# BS01_and_BA01_Connectors.net
KiCad netlist of a schematic drawn in Altium Designer
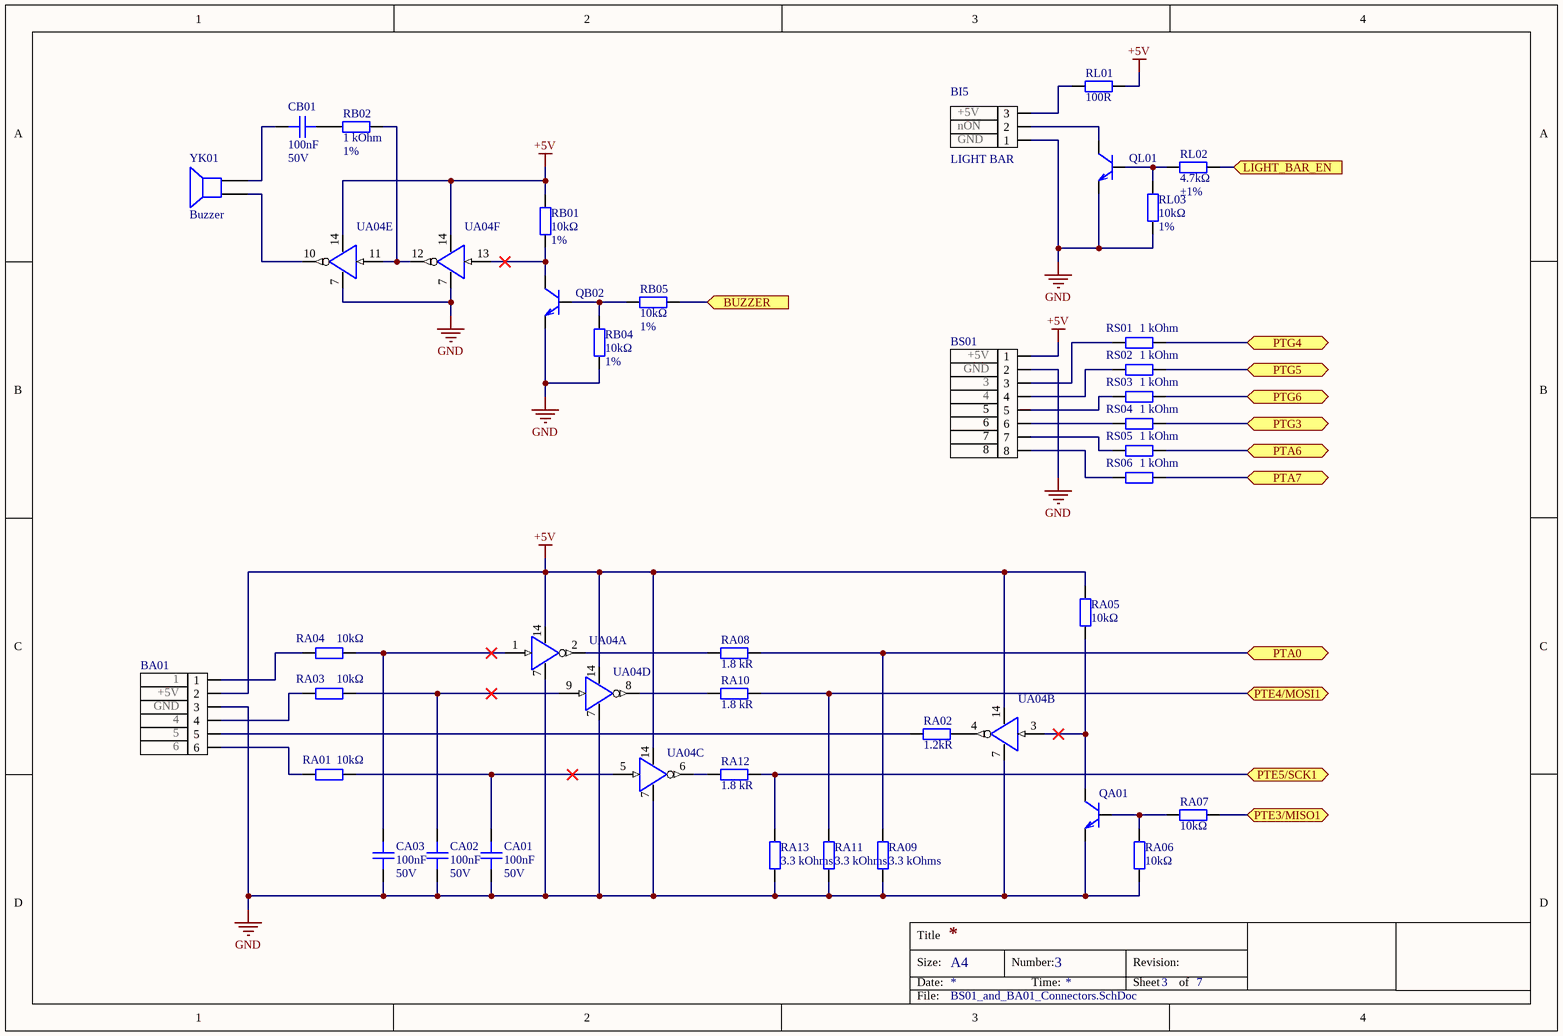
[diagram p0: BS01_and_BA01_Connectors.SchDoc]

(export (version "E")
  (design (tool "Eeschema 10.0.6"))
  (components
    (comp (ref "BA01")
      (value "Comment")
      (fields
        (field (name "PIN_1") "1")
        (field (name "PIN_2") "+5V")
        (field (name "PIN_3") "GND")
        (field (name "PIN_4") "4")
        (field (name "PIN_5") "5")
        (field (name "PIN_6") "6")
      )
      (libsource (lib "connectors_header") (part "CONN HEADER EC 6POS"))
    )
    (comp (ref "BI5")
      (value "LIGHT BAR")
      (footprint "CONN_S3B-ZR_JST")
      (description "Connector Header Through Hole, Right Angle 3 position 0.059\" (1.50mm)")
      (fields
        (field (name "MANUFACTURER") "JST")
        (field (name "MANUFACTURER PART NUMBER") "S3B-ZR(LF)(SN)")
        (field (name "PIN_1") "GND")
        (field (name "PIN_2") "nON")
        (field (name "PIN_3") "+5V")
      )
      (libsource (lib "connectors_header") (part "CONN HEADER TH R/A 3POS 1.5MM"))
    )
    (comp (ref "BS01")
      (value "CONN HEADER R/A 8POS 2.54MM")
      (footprint "CONN HEADER R/A 8POS 2.54MM")
      (description "Connector Header Through Hole, Right Angle 8 position 0.100\" (2.54mm)")
      (fields
        (field (name "PIN_1") "+5V")
        (field (name "PIN_2") "GND")
        (field (name "PIN_3") "3")
        (field (name "PIN_4") "4")
        (field (name "PIN_7") "7")
        (field (name "PIN_5") "5")
        (field (name "PIN_6") "6")
        (field (name "PIN_8") "8")
      )
      (libsource (lib "connectors_header") (part "CONN HEADER R/A 8POS 2.54MM"))
    )
    (comp (ref "CA01")
      (value "CAP CER 0.1uF ±10% 50V X7R 0603")
      (footprint "CAPC1608X08N_0603")
      (description "Capacitor")
      (fields
        (field (name "MANUFACTURER") "KEMET")
        (field (name "MANUFACTURER PART NUMBER") "C0603C104M5RACTU")
        (field (name "CAPACITANCE") "100nF")
        (field (name "VOLTAGE RATING") "50V")
      )
      (libsource (lib "capacitors_smd") (part "CAP CER 0.1uF ±10% 50V X7R 0603"))
    )
    (comp (ref "CA02")
      (value "CAP CER 0.1uF ±10% 50V X7R 0603")
      (footprint "CAPC1608X08N_0603")
      (description "Capacitor")
      (fields
        (field (name "MANUFACTURER") "KEMET")
        (field (name "MANUFACTURER PART NUMBER") "C0603C104M5RACTU")
        (field (name "CAPACITANCE") "100nF")
        (field (name "VOLTAGE RATING") "50V")
      )
      (libsource (lib "capacitors_smd") (part "CAP CER 0.1uF ±10% 50V X7R 0603"))
    )
    (comp (ref "CA03")
      (value "CAP CER 0.1uF ±10% 50V X7R 0603")
      (footprint "CAPC1608X08N_0603")
      (description "Capacitor")
      (fields
        (field (name "MANUFACTURER") "KEMET")
        (field (name "MANUFACTURER PART NUMBER") "C0603C104M5RACTU")
        (field (name "CAPACITANCE") "100nF")
        (field (name "VOLTAGE RATING") "50V")
      )
      (libsource (lib "capacitors_smd") (part "CAP CER 0.1uF ±10% 50V X7R 0603"))
    )
    (comp (ref "CB01")
      (value "CAP CER 0.1uF ±10% 50V X7R 0603")
      (footprint "CAPC1608X08N_0603")
      (description "Capacitor")
      (fields
        (field (name "MANUFACTURER") "KEMET")
        (field (name "MANUFACTURER PART NUMBER") "C0603C104M5RACTU")
        (field (name "CAPACITANCE") "100nF")
        (field (name "VOLTAGE RATING") "50V")
      )
      (libsource (lib "capacitors_smd") (part "CAP CER 0.1uF ±10% 50V X7R 0603"))
    )
    (comp (ref "QA01")
      (value "BC847CW,115")
      (footprint "SOT-323")
      (description "Bipolar (BJT) Transistor NPN 45V 100mA 100MHz 200mW Surface Mount SOT-323-3")
      (fields (field (name "MANUFACTURER") "Nexperia"))
      (libsource (lib "bipolar-junction_transistors") (part "TRANS BC847CW,115 NPN 45V 0.1A SOT323"))
    )
    (comp (ref "QB02")
      (value "BC847CW,115")
      (footprint "SOT-323")
      (description "Bipolar (BJT) Transistor NPN 45V 100mA 100MHz 200mW Surface Mount SOT-323-3")
      (fields (field (name "MANUFACTURER") "Nexperia"))
      (libsource (lib "bipolar-junction_transistors") (part "TRANS BC847CW,115 NPN 45V 0.1A SOT323"))
    )
    (comp (ref "QL01")
      (value "BC847CW,115")
      (footprint "SOT-323")
      (description "Bipolar (BJT) Transistor NPN 45V 100mA 100MHz 200mW Surface Mount SOT-323-3")
      (fields (field (name "MANUFACTURER") "Nexperia"))
      (libsource (lib "bipolar-junction_transistors") (part "TRANS BC847CW,115 NPN 45V 0.1A SOT323"))
    )
    (comp (ref "RA01")
      (value "RES SMD 10K OHM 1% 1/10W 0603")
      (footprint "R0603")
      (description "10 kOhms ±1% 0.1W, 1/10W Chip Resistor 0603 (1608 Metric)  Thick Film")
      (fields
        (field (name "MANUFACTURER") "Yageo")
        (field (name "MANUFACTURER PART NUMBER") "RC0603FR-0710KL")
        (field (name "RESISTANCE") "10kΩ")
      )
      (libsource (lib "") (part "RES SMD 10K OHM 1% 1/10W 0603_1"))
    )
    (comp (ref "RA02")
      (value "RES SMD 1.2K OHM 1% 1/16W 0402")
      (footprint "R0402")
      (description "1.2 kOhms ±1% 0.063W, 1/16W Chip Resistor 0402 (1005 Metric) Moisture Resistant Thick Film")
      (fields
        (field (name "MANUFACTURER") "Yageo")
        (field (name "MANUFACTURER PART NUMBER") "RC0402FR-071K2L")
        (field (name "RESISTANCE") "1.2kR")
      )
      (libsource (lib "resistors_smd") (part "RES SMD 1.2K OHM 1% 1/16W 0402"))
    )
    (comp (ref "RA03")
      (value "RES SMD 10K OHM 1% 1/10W 0603")
      (footprint "R0603")
      (description "10 kOhms ±1% 0.1W, 1/10W Chip Resistor 0603 (1608 Metric)  Thick Film")
      (fields
        (field (name "MANUFACTURER") "Yageo")
        (field (name "MANUFACTURER PART NUMBER") "RC0603FR-0710KL")
        (field (name "RESISTANCE") "10kΩ")
      )
      (libsource (lib "") (part "RES SMD 10K OHM 1% 1/10W 0603_1"))
    )
    (comp (ref "RA04")
      (value "RES SMD 10K OHM 1% 1/10W 0603")
      (footprint "R0603")
      (description "10 kOhms ±1% 0.1W, 1/10W Chip Resistor 0603 (1608 Metric)  Thick Film")
      (fields
        (field (name "MANUFACTURER") "Yageo")
        (field (name "MANUFACTURER PART NUMBER") "RC0603FR-0710KL")
        (field (name "RESISTANCE") "10kΩ")
      )
      (libsource (lib "") (part "RES SMD 10K OHM 1% 1/10W 0603_1"))
    )
    (comp (ref "RA05")
      (value "RES SMD 10K OHM 1% 1/10W 0603")
      (footprint "R0603")
      (description "10 kOhms ±1% 0.1W, 1/10W Chip Resistor 0603 (1608 Metric)  Thick Film")
      (fields
        (field (name "MANUFACTURER") "Yageo")
        (field (name "MANUFACTURER PART NUMBER") "RC0603FR-0710KL")
        (field (name "RESISTANCE") "10kΩ")
      )
      (libsource (lib "") (part "RES SMD 10K OHM 1% 1/10W 0603_2"))
    )
    (comp (ref "RA06")
      (value "RES SMD 10K OHM 1% 1/10W 0603")
      (footprint "R0603")
      (description "10 kOhms ±1% 0.1W, 1/10W Chip Resistor 0603 (1608 Metric)  Thick Film")
      (fields
        (field (name "MANUFACTURER") "Yageo")
        (field (name "MANUFACTURER PART NUMBER") "RC0603FR-0710KL")
        (field (name "RESISTANCE") "10kΩ")
      )
      (libsource (lib "") (part "RES SMD 10K OHM 1% 1/10W 0603_2"))
    )
    (comp (ref "RA07")
      (value "RES SMD 10K OHM 1% 1/10W 0603")
      (footprint "R0603")
      (description "10 kOhms ±1% 0.1W, 1/10W Chip Resistor 0603 (1608 Metric)  Thick Film")
      (fields
        (field (name "MANUFACTURER") "Yageo")
        (field (name "MANUFACTURER PART NUMBER") "RC0603FR-0710KL")
        (field (name "RESISTANCE") "10kΩ")
      )
      (libsource (lib "resistors_smd") (part "RES SMD 10K OHM 1% 1/10W 0603"))
    )
    (comp (ref "RA08")
      (value "RES SMD 1.91K OHM 1% 1/16W 0402")
      (footprint "R0402")
      (description "1.91 kOhms ±1% 0.063W, 1/16W Chip Resistor 0402 (1005 Metric) Moisture Resistant Thick Film")
      (fields
        (field (name "MANUFACTURER") "Yageo")
        (field (name "MANUFACTURER PART NUMBER") "RC0402FR-071K91L")
        (field (name "RESISTANCE") "1.8 kR")
      )
      (libsource (lib "resistors_smd") (part "RES SMD 1.91K OHM 1% 1/16W 0402"))
    )
    (comp (ref "RA09")
      (value "3.3 kOhms")
      (footprint "R_0603")
      (description "RES SMD 3.3K OHM 1% 1/4W 0603")
      (fields
        (field (name "DIGI-KEYPARTNUMBER") "541-3.30KSCT-ND")
        (field (name "PARTNUMBER") "CRCW06033K30FKEAHP")
      )
      (libsource (lib "resistors_smd") (part "RES_SMD_3.3K_OHM_1%_1/4W_0603"))
    )
    (comp (ref "RA10")
      (value "RES SMD 1.91K OHM 1% 1/16W 0402")
      (footprint "R0402")
      (description "1.91 kOhms ±1% 0.063W, 1/16W Chip Resistor 0402 (1005 Metric) Moisture Resistant Thick Film")
      (fields
        (field (name "MANUFACTURER") "Yageo")
        (field (name "MANUFACTURER PART NUMBER") "RC0402FR-071K91L")
        (field (name "RESISTANCE") "1.8 kR")
      )
      (libsource (lib "resistors_smd") (part "RES SMD 1.91K OHM 1% 1/16W 0402"))
    )
    (comp (ref "RA11")
      (value "3.3 kOhms")
      (footprint "R_0603")
      (description "RES SMD 3.3K OHM 1% 1/4W 0603")
      (fields
        (field (name "DIGI-KEYPARTNUMBER") "541-3.30KSCT-ND")
        (field (name "PARTNUMBER") "CRCW06033K30FKEAHP")
      )
      (libsource (lib "resistors_smd") (part "RES_SMD_3.3K_OHM_1%_1/4W_0603"))
    )
    (comp (ref "RA12")
      (value "RES SMD 1.91K OHM 1% 1/16W 0402")
      (footprint "R0402")
      (description "1.91 kOhms ±1% 0.063W, 1/16W Chip Resistor 0402 (1005 Metric) Moisture Resistant Thick Film")
      (fields
        (field (name "MANUFACTURER") "Yageo")
        (field (name "MANUFACTURER PART NUMBER") "RC0402FR-071K91L")
        (field (name "RESISTANCE") "1.8 kR")
      )
      (libsource (lib "resistors_smd") (part "RES SMD 1.91K OHM 1% 1/16W 0402"))
    )
    (comp (ref "RA13")
      (value "3.3 kOhms")
      (footprint "R_0603")
      (description "RES SMD 3.3K OHM 1% 1/4W 0603")
      (fields
        (field (name "DIGI-KEYPARTNUMBER") "541-3.30KSCT-ND")
        (field (name "PARTNUMBER") "CRCW06033K30FKEAHP")
      )
      (libsource (lib "resistors_smd") (part "RES_SMD_3.3K_OHM_1%_1/4W_0603"))
    )
    (comp (ref "RB01")
      (value "RES SMD 10K OHM 1% 1/10W 0603")
      (footprint "R0603")
      (description "10 kOhms ±1% 0.1W, 1/10W Chip Resistor 0603 (1608 Metric)  Thick Film")
      (fields
        (field (name "MANUFACTURER") "Yageo")
        (field (name "MANUFACTURER PART NUMBER") "RC0603FR-0710KL")
        (field (name "RESISTANCE") "10kΩ")
        (field (name "TOLERANCE") "1%")
      )
      (libsource (lib "resistors_smd") (part "RES SMD 10K OHM 1% 1/10W 0603"))
    )
    (comp (ref "RB02")
      (value "1 kOhms ±1% 0.1W, 1/10W Chip Resistor 0603 (1608 Metric) Moisture Resistant Thick Film")
      (footprint "R0603")
      (fields
        (field (name "MANUFACTURER") "Yageo")
        (field (name "MANUFACTURER PART NUMBER") "RC0603FR-071KL")
        (field (name "RESISTANCE") "1 kOhm")
        (field (name "TOLERANCE") "1%")
      )
      (libsource (lib "resistors_smd") (part "RES SMD 1K OHM 1% 1/10W 0603"))
    )
    (comp (ref "RB04")
      (value "RES SMD 10K OHM 1% 1/10W 0603")
      (footprint "R0603")
      (description "10 kOhms ±1% 0.1W, 1/10W Chip Resistor 0603 (1608 Metric)  Thick Film")
      (fields
        (field (name "MANUFACTURER") "Yageo")
        (field (name "MANUFACTURER PART NUMBER") "RC0603FR-0710KL")
        (field (name "RESISTANCE") "10kΩ")
        (field (name "TOLERANCE") "1%")
      )
      (libsource (lib "resistors_smd") (part "RES SMD 10K OHM 1% 1/10W 0603"))
    )
    (comp (ref "RB05")
      (value "RES SMD 10K OHM 1% 1/10W 0603")
      (footprint "R0603")
      (description "10 kOhms ±1% 0.1W, 1/10W Chip Resistor 0603 (1608 Metric)  Thick Film")
      (fields
        (field (name "MANUFACTURER") "Yageo")
        (field (name "MANUFACTURER PART NUMBER") "RC0603FR-0710KL")
        (field (name "RESISTANCE") "10kΩ")
        (field (name "TOLERANCE") "1%")
      )
      (libsource (lib "") (part "RES SMD 10K OHM 1% 1/10W 0603_2"))
    )
    (comp (ref "RL01")
      (value "~")
      (footprint "Anthem Projects:R_0805")
      (fields
        (field (name "MANUFACTURER") "Panasonic")
        (field (name "MANUFACTURER PART NUMBER") "ERJ-P6WF1000V")
        (field (name "RESISTANCE") "100R")
        (field (name "TOLERANCE") "1%")
      )
      (libsource (lib "resistors_smd") (part "RES SMD 100 OHM 1% 1/2W 0805"))
    )
    (comp (ref "RL02")
      (value "~")
      (footprint "Resistor-0603")
      (description "Resistor")
      (fields
        (field (name "MANUFACTURER") "Yageo")
        (field (name "MANUFACTURER PART NUMBER") "AC0603FR-074K7L")
        (field (name "RESISTANCE") "4.7kΩ")
        (field (name "TOLERANCE") "±1%")
      )
      (libsource (lib "resistors_smd") (part "R 4.7kΩ ±1% 0603 0.1W"))
    )
    (comp (ref "RL03")
      (value "RES SMD 10K OHM 1% 1/10W 0603")
      (footprint "R0603")
      (description "10 kOhms ±1% 0.1W, 1/10W Chip Resistor 0603 (1608 Metric)  Thick Film")
      (fields
        (field (name "MANUFACTURER") "Yageo")
        (field (name "MANUFACTURER PART NUMBER") "RC0603FR-0710KL")
        (field (name "RESISTANCE") "10kΩ")
        (field (name "TOLERANCE") "1%")
      )
      (libsource (lib "resistors_smd") (part "RES SMD 10K OHM 1% 1/10W 0603"))
    )
    (comp (ref "RS01")
      (value "1 kOhms ±1% 0.1W, 1/10W Chip Resistor 0603 (1608 Metric) Moisture Resistant Thick Film")
      (footprint "R0603")
      (fields
        (field (name "MANUFACTURER") "Yageo")
        (field (name "MANUFACTURER PART NUMBER") "RC0603FR-071KL")
        (field (name "TOLERANCE") "1%")
        (field (name "RESISTANCE") "1 kOhm")
      )
      (libsource (lib "") (part "RES SMD 1K OHM 1% 1/10W 0603_1"))
    )
    (comp (ref "RS02")
      (value "1 kOhms ±1% 0.1W, 1/10W Chip Resistor 0603 (1608 Metric) Moisture Resistant Thick Film")
      (footprint "R0603")
      (fields
        (field (name "MANUFACTURER") "Yageo")
        (field (name "MANUFACTURER PART NUMBER") "RC0603FR-071KL")
        (field (name "TOLERANCE") "1%")
        (field (name "RESISTANCE") "1 kOhm")
      )
      (libsource (lib "") (part "RES SMD 1K OHM 1% 1/10W 0603_1"))
    )
    (comp (ref "RS03")
      (value "1 kOhms ±1% 0.1W, 1/10W Chip Resistor 0603 (1608 Metric) Moisture Resistant Thick Film")
      (footprint "R0603")
      (fields
        (field (name "MANUFACTURER") "Yageo")
        (field (name "MANUFACTURER PART NUMBER") "RC0603FR-071KL")
        (field (name "TOLERANCE") "1%")
        (field (name "RESISTANCE") "1 kOhm")
      )
      (libsource (lib "") (part "RES SMD 1K OHM 1% 1/10W 0603_1"))
    )
    (comp (ref "RS04")
      (value "1 kOhms ±1% 0.1W, 1/10W Chip Resistor 0603 (1608 Metric) Moisture Resistant Thick Film")
      (footprint "R0603")
      (fields
        (field (name "MANUFACTURER") "Yageo")
        (field (name "MANUFACTURER PART NUMBER") "RC0603FR-071KL")
        (field (name "TOLERANCE") "1%")
        (field (name "RESISTANCE") "1 kOhm")
      )
      (libsource (lib "") (part "RES SMD 1K OHM 1% 1/10W 0603_1"))
    )
    (comp (ref "RS05")
      (value "1 kOhms ±1% 0.1W, 1/10W Chip Resistor 0603 (1608 Metric) Moisture Resistant Thick Film")
      (footprint "R0603")
      (fields
        (field (name "MANUFACTURER") "Yageo")
        (field (name "MANUFACTURER PART NUMBER") "RC0603FR-071KL")
        (field (name "TOLERANCE") "1%")
        (field (name "RESISTANCE") "1 kOhm")
      )
      (libsource (lib "") (part "RES SMD 1K OHM 1% 1/10W 0603_1"))
    )
    (comp (ref "RS06")
      (value "1 kOhms ±1% 0.1W, 1/10W Chip Resistor 0603 (1608 Metric) Moisture Resistant Thick Film")
      (footprint "R0603")
      (fields
        (field (name "MANUFACTURER") "Yageo")
        (field (name "MANUFACTURER PART NUMBER") "RC0603FR-071KL")
        (field (name "TOLERANCE") "1%")
        (field (name "RESISTANCE") "1 kOhm")
      )
      (libsource (lib "") (part "RES SMD 1K OHM 1% 1/10W 0603_1"))
    )
    (comp (ref "UA04")
      (value "IC SN74AC14D INVERT SCHMITT 6CH 6IN 14SOIC")
      (description "Inverter IC 6 Channel Schmitt Trigger 14-SOIC")
      (fields
        (field (name "MANUFACTURER") "ON Semiconductor / Fairchild")
        (field (name "MANUFACTURER PART NUMBER") "74AC14SCX")
      )
      (libsource (lib "ic_logic") (part "IC SN74AC14D INVERT SCHMITT 6CH 6IN 14SOIC"))
    )
    (comp (ref "YK01")
      (value "Buzzer")
      (footprint "PIN2")
      (description "Loudspeaker")
      (fields (field (name "PUBLISHER") "Altium Limited"))
      (libsource (lib "Miscellaneous Devices") (part "Speaker"))
    )
  )
  (nets
    (net (code "1") (name "+5V") (class "Default")
      (node (ref "BA01") (pin "2") (pinfunction "2_2") (pintype "passive"))
      (node (ref "BS01") (pin "1") (pinfunction "1_1") (pintype "passive"))
      (node (ref "RA05") (pin "1") (pinfunction "1_1") (pintype "passive"))
      (node (ref "RB01") (pin "2") (pinfunction "2_2") (pintype "passive"))
      (node (ref "RL01") (pin "1") (pinfunction "1_1") (pintype "passive"))
      (node (ref "UA04") (pin "14") (pinfunction "VCC_14") (pintype "power_in"))
    )
    (net (code "2") (name "/BUZZER") (class "Default")
      (node (ref "RB05") (pin "1") (pinfunction "1_1") (pintype "passive"))
    )
    (net (code "3") (name "/LIGHT_BAR_EN") (class "Default")
      (node (ref "RL02") (pin "2") (pinfunction "2_2") (pintype "passive"))
    )
    (net (code "4") (name "/PTA0") (class "Default")
      (node (ref "RA08") (pin "2") (pinfunction "2_2") (pintype "passive"))
      (node (ref "RA09") (pin "1") (pinfunction "1_1") (pintype "passive"))
    )
    (net (code "5") (name "/PTA6") (class "Default")
      (node (ref "RS05") (pin "2") (pinfunction "2_2") (pintype "passive"))
    )
    (net (code "6") (name "/PTA7") (class "Default")
      (node (ref "RS06") (pin "2") (pinfunction "2_2") (pintype "passive"))
    )
    (net (code "7") (name "/PTE3{slash}MISO1") (class "Default")
      (node (ref "RA07") (pin "2") (pinfunction "2_2") (pintype "passive"))
    )
    (net (code "8") (name "/PTE4{slash}MOSI1") (class "Default")
      (node (ref "RA10") (pin "2") (pinfunction "2_2") (pintype "passive"))
      (node (ref "RA11") (pin "1") (pinfunction "1_1") (pintype "passive"))
    )
    (net (code "9") (name "/PTE5{slash}SCK1") (class "Default")
      (node (ref "RA12") (pin "2") (pinfunction "2_2") (pintype "passive"))
      (node (ref "RA13") (pin "1") (pinfunction "1_1") (pintype "passive"))
    )
    (net (code "10") (name "/PTG3") (class "Default")
      (node (ref "RS04") (pin "2") (pinfunction "2_2") (pintype "passive"))
    )
    (net (code "11") (name "/PTG4") (class "Default")
      (node (ref "RS01") (pin "2") (pinfunction "2_2") (pintype "passive"))
    )
    (net (code "12") (name "/PTG5") (class "Default")
      (node (ref "RS02") (pin "2") (pinfunction "2_2") (pintype "passive"))
    )
    (net (code "13") (name "/PTG6") (class "Default")
      (node (ref "RS03") (pin "2") (pinfunction "2_2") (pintype "passive"))
    )
    (net (code "14") (name "GND") (class "Default")
      (node (ref "BA01") (pin "3") (pinfunction "3_3") (pintype "passive"))
      (node (ref "BI5") (pin "1") (pinfunction "1_1") (pintype "passive"))
      (node (ref "BS01") (pin "2") (pinfunction "2_2") (pintype "passive"))
      (node (ref "CA01") (pin "1") (pinfunction "1_1") (pintype "passive"))
      (node (ref "CA02") (pin "1") (pinfunction "1_1") (pintype "passive"))
      (node (ref "CA03") (pin "1") (pinfunction "1_1") (pintype "passive"))
      (node (ref "QA01") (pin "2") (pinfunction "E_2") (pintype "passive"))
      (node (ref "QB02") (pin "2") (pinfunction "E_2") (pintype "passive"))
      (node (ref "QL01") (pin "2") (pinfunction "E_2") (pintype "passive"))
      (node (ref "RA06") (pin "2") (pinfunction "2_2") (pintype "passive"))
      (node (ref "RA09") (pin "2") (pinfunction "2_2") (pintype "passive"))
      (node (ref "RA11") (pin "2") (pinfunction "2_2") (pintype "passive"))
      (node (ref "RA13") (pin "2") (pinfunction "2_2") (pintype "passive"))
      (node (ref "RB04") (pin "1") (pinfunction "1_1") (pintype "passive"))
      (node (ref "RL03") (pin "1") (pinfunction "1_1") (pintype "passive"))
      (node (ref "UA04") (pin "7") (pinfunction "GND_7") (pintype "power_in"))
    )
    (net (code "15") (name "Net-(BA01-Pad1)") (class "Default")
      (node (ref "BA01") (pin "1") (pinfunction "1_1") (pintype "passive"))
      (node (ref "RA04") (pin "2") (pinfunction "2_2") (pintype "passive"))
    )
    (net (code "16") (name "Net-(BA01-Pad4)") (class "Default")
      (node (ref "BA01") (pin "4") (pinfunction "4_4") (pintype "passive"))
      (node (ref "RA03") (pin "2") (pinfunction "2_2") (pintype "passive"))
    )
    (net (code "17") (name "Net-(BA01-Pad5)") (class "Default")
      (node (ref "BA01") (pin "5") (pinfunction "5_5") (pintype "passive"))
      (node (ref "RA02") (pin "1") (pinfunction "1_1") (pintype "passive"))
    )
    (net (code "18") (name "Net-(BA01-Pad6)") (class "Default")
      (node (ref "BA01") (pin "6") (pinfunction "6_6") (pintype "passive"))
      (node (ref "RA01") (pin "2") (pinfunction "2_2") (pintype "passive"))
    )
    (net (code "19") (name "Net-(BI5-Pad3)") (class "Default")
      (node (ref "BI5") (pin "3") (pinfunction "3_3") (pintype "passive"))
      (node (ref "RL01") (pin "2") (pinfunction "2_2") (pintype "passive"))
    )
    (net (code "20") (name "Net-(BS01-Pad3)") (class "Default")
      (node (ref "BS01") (pin "3") (pinfunction "3_3") (pintype "passive"))
      (node (ref "RS01") (pin "1") (pinfunction "1_1") (pintype "passive"))
    )
    (net (code "21") (name "Net-(BS01-Pad4)") (class "Default")
      (node (ref "BS01") (pin "4") (pinfunction "4_4") (pintype "passive"))
      (node (ref "RS02") (pin "1") (pinfunction "1_1") (pintype "passive"))
    )
    (net (code "22") (name "Net-(BS01-Pad5)") (class "Default")
      (node (ref "BS01") (pin "5") (pinfunction "5_5") (pintype "passive"))
      (node (ref "RS03") (pin "1") (pinfunction "1_1") (pintype "passive"))
    )
    (net (code "23") (name "Net-(BS01-Pad6)") (class "Default")
      (node (ref "BS01") (pin "6") (pinfunction "6_6") (pintype "passive"))
      (node (ref "RS04") (pin "1") (pinfunction "1_1") (pintype "passive"))
    )
    (net (code "24") (name "Net-(BS01-Pad7)") (class "Default")
      (node (ref "BS01") (pin "7") (pinfunction "7_7") (pintype "passive"))
      (node (ref "RS05") (pin "1") (pinfunction "1_1") (pintype "passive"))
    )
    (net (code "25") (name "Net-(BS01-Pad8)") (class "Default")
      (node (ref "BS01") (pin "8") (pinfunction "8_8") (pintype "passive"))
      (node (ref "RS06") (pin "1") (pinfunction "1_1") (pintype "passive"))
    )
    (net (code "26") (name "Net-(CB01-Pad1)") (class "Default")
      (node (ref "CB01") (pin "1") (pinfunction "1_1") (pintype "passive"))
      (node (ref "YK01") (pin "2") (pinfunction "2_2") (pintype "passive"))
    )
    (net (code "27") (name "Net-(CB01-Pad2)") (class "Default")
      (node (ref "CB01") (pin "2") (pinfunction "2_2") (pintype "passive"))
      (node (ref "RB02") (pin "2") (pinfunction "2_2") (pintype "passive"))
    )
    (net (code "28") (name "Net-(QA01-B)") (class "Default")
      (node (ref "QA01") (pin "1") (pinfunction "B_1") (pintype "passive"))
      (node (ref "RA06") (pin "1") (pinfunction "1_1") (pintype "passive"))
      (node (ref "RA07") (pin "1") (pinfunction "1_1") (pintype "passive"))
    )
    (net (code "29") (name "Net-(QA01-C)") (class "Default")
      (node (ref "QA01") (pin "3") (pinfunction "C_3") (pintype "passive"))
      (node (ref "RA05") (pin "2") (pinfunction "2_2") (pintype "passive"))
      (node (ref "UA04") (pin "3") (pinfunction "2A_3") (pintype "input"))
    )
    (net (code "30") (name "Net-(QB02-B)") (class "Default")
      (node (ref "QB02") (pin "1") (pinfunction "B_1") (pintype "passive"))
      (node (ref "RB04") (pin "2") (pinfunction "2_2") (pintype "passive"))
      (node (ref "RB05") (pin "2") (pinfunction "2_2") (pintype "passive"))
    )
    (net (code "31") (name "Net-(QB02-C)") (class "Default")
      (node (ref "QB02") (pin "3") (pinfunction "C_3") (pintype "passive"))
      (node (ref "RB01") (pin "1") (pinfunction "1_1") (pintype "passive"))
      (node (ref "UA04") (pin "13") (pinfunction "6A_13") (pintype "input"))
    )
    (net (code "32") (name "Net-(QL01-B)") (class "Default")
      (node (ref "QL01") (pin "1") (pinfunction "B_1") (pintype "passive"))
      (node (ref "RL02") (pin "1") (pinfunction "1_1") (pintype "passive"))
      (node (ref "RL03") (pin "2") (pinfunction "2_2") (pintype "passive"))
    )
    (net (code "33") (name "Net-(QL01-C)") (class "Default")
      (node (ref "BI5") (pin "2") (pinfunction "2_2") (pintype "passive"))
      (node (ref "QL01") (pin "3") (pinfunction "C_3") (pintype "passive"))
    )
    (net (code "34") (name "Net-(UA04A-1A)") (class "Default")
      (node (ref "CA03") (pin "2") (pinfunction "2_2") (pintype "passive"))
      (node (ref "RA04") (pin "1") (pinfunction "1_1") (pintype "passive"))
      (node (ref "UA04") (pin "1") (pinfunction "1A_1") (pintype "input"))
    )
    (net (code "35") (name "Net-(UA04A-1Y)") (class "Default")
      (node (ref "RA08") (pin "1") (pinfunction "1_1") (pintype "passive"))
      (node (ref "UA04") (pin "2") (pinfunction "1Y_2") (pintype "output"))
    )
    (net (code "36") (name "Net-(UA04B-2Y)") (class "Default")
      (node (ref "RA02") (pin "2") (pinfunction "2_2") (pintype "passive"))
      (node (ref "UA04") (pin "4") (pinfunction "2Y_4") (pintype "output"))
    )
    (net (code "37") (name "Net-(UA04C-3A)") (class "Default")
      (node (ref "CA01") (pin "2") (pinfunction "2_2") (pintype "passive"))
      (node (ref "RA01") (pin "1") (pinfunction "1_1") (pintype "passive"))
      (node (ref "UA04") (pin "5") (pinfunction "3A_5") (pintype "input"))
    )
    (net (code "38") (name "Net-(UA04C-3Y)") (class "Default")
      (node (ref "RA12") (pin "1") (pinfunction "1_1") (pintype "passive"))
      (node (ref "UA04") (pin "6") (pinfunction "3Y_6") (pintype "output"))
    )
    (net (code "39") (name "Net-(UA04D-4A)") (class "Default")
      (node (ref "CA02") (pin "2") (pinfunction "2_2") (pintype "passive"))
      (node (ref "RA03") (pin "1") (pinfunction "1_1") (pintype "passive"))
      (node (ref "UA04") (pin "9") (pinfunction "4A_9") (pintype "input"))
    )
    (net (code "40") (name "Net-(UA04D-4Y)") (class "Default")
      (node (ref "RA10") (pin "1") (pinfunction "1_1") (pintype "passive"))
      (node (ref "UA04") (pin "8") (pinfunction "4Y_8") (pintype "output"))
    )
    (net (code "41") (name "Net-(UA04E-5A)") (class "Default")
      (node (ref "RB02") (pin "1") (pinfunction "1_1") (pintype "passive"))
      (node (ref "UA04") (pin "11") (pinfunction "5A_11") (pintype "input"))
      (node (ref "UA04") (pin "12") (pinfunction "6Y_12") (pintype "output"))
    )
    (net (code "42") (name "Net-(UA04E-5Y)") (class "Default")
      (node (ref "UA04") (pin "10") (pinfunction "5Y_10") (pintype "output"))
      (node (ref "YK01") (pin "1") (pinfunction "1_1") (pintype "passive"))
    )
  )
)
